# ludusProtoShield.net
KiCad netlist of a schematic drawn in EAGLE
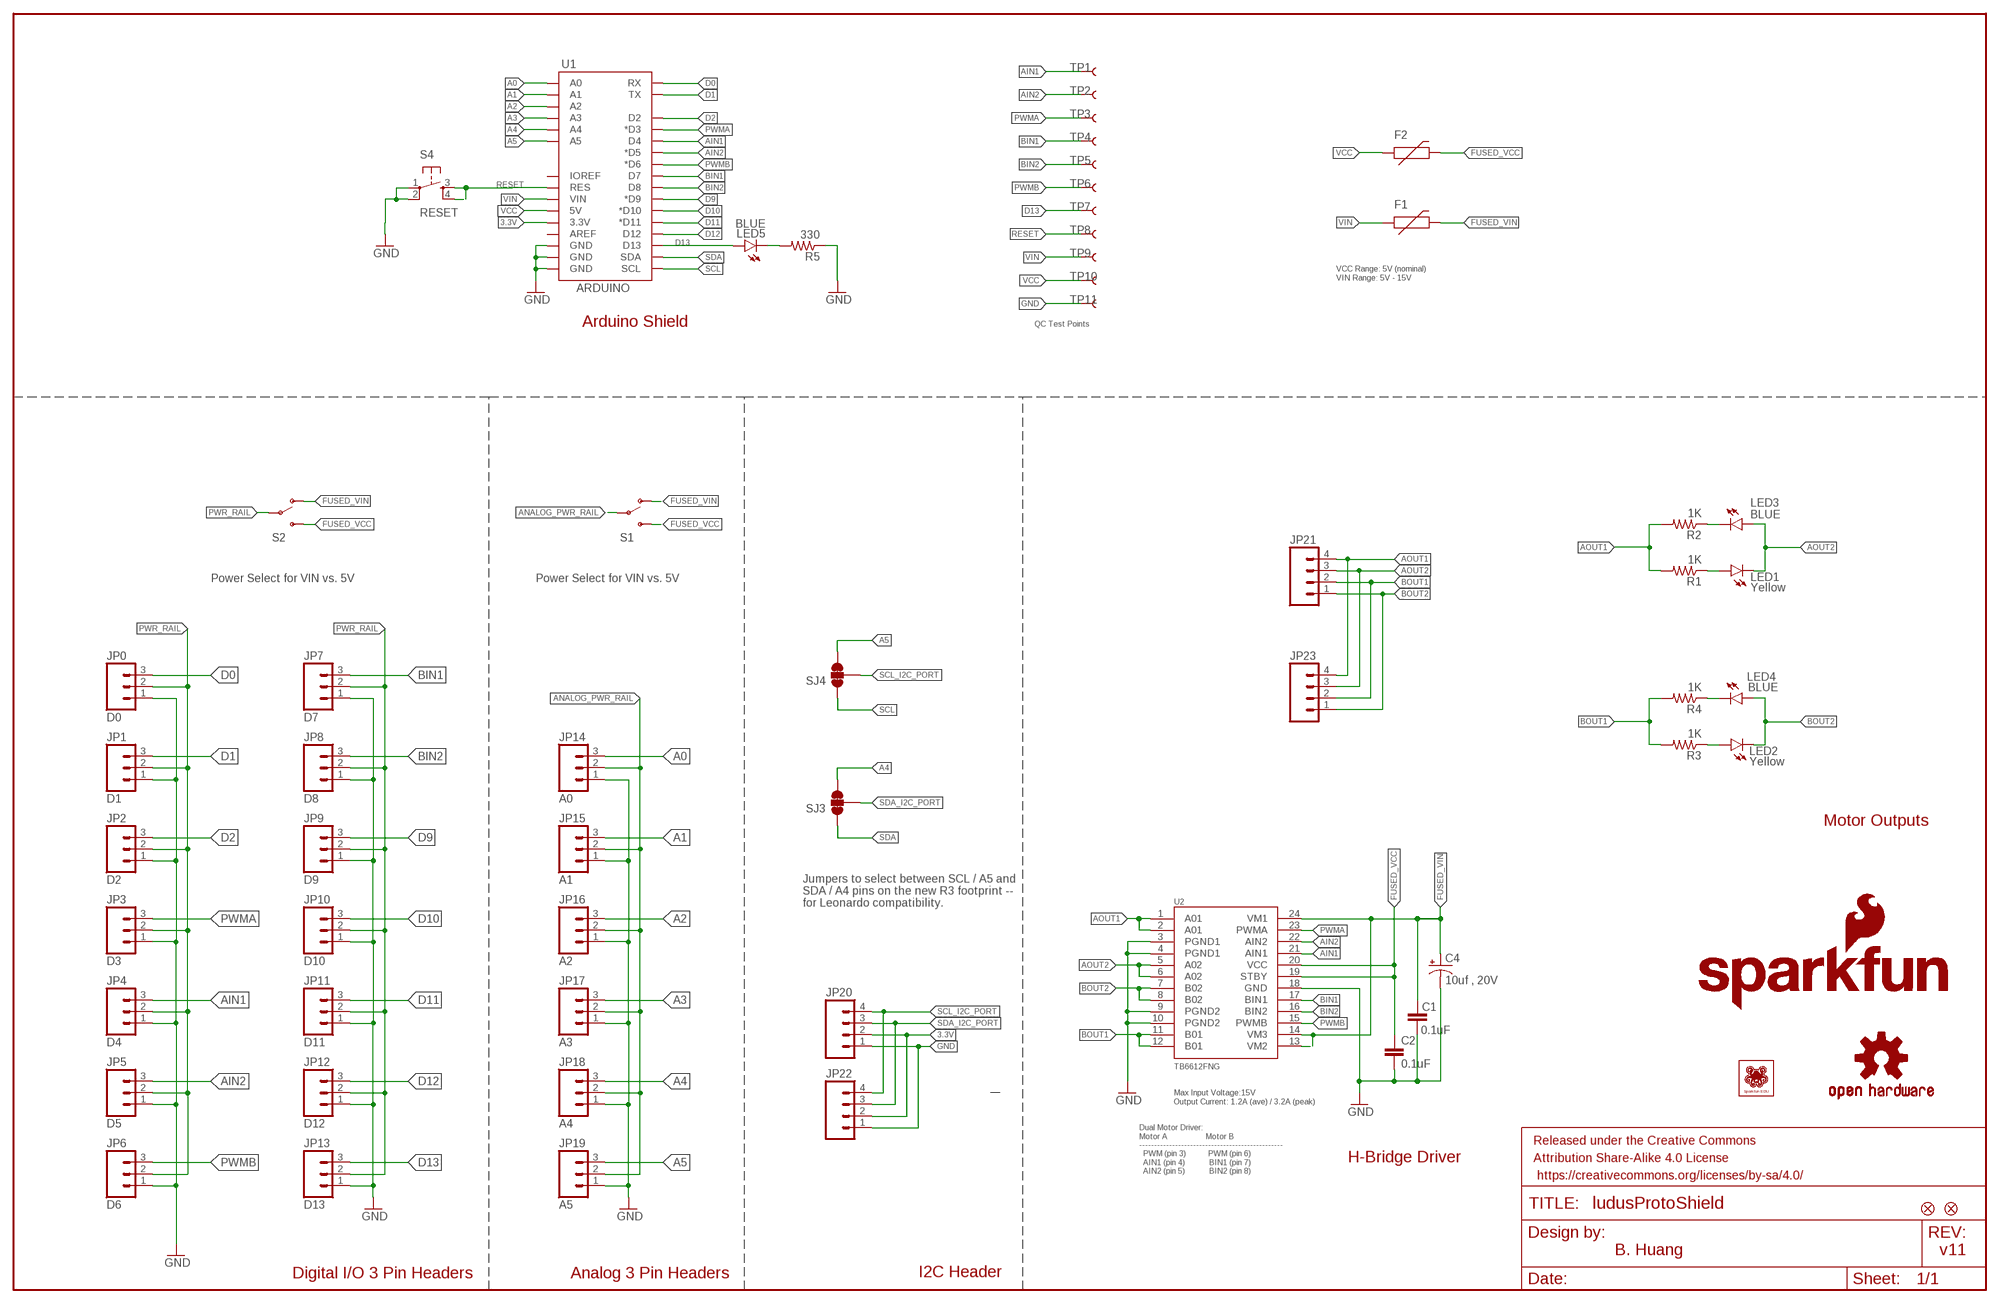
[diagram p0: schematic, sheet 1]

(export (version "E")
  (design (tool "Eeschema 10.0.6"))
  (components
    (comp (ref "C1")
      (value "0.1uF")
      (footprint "eagle-import:0603-CAP")
      (libsource (lib "eagle-import") (part "0.1UF-25V-5%(0603)"))
    )
    (comp (ref "C2")
      (value "0.1uF")
      (footprint "eagle-import:0603-CAP")
      (libsource (lib "eagle-import") (part "0.1UF-25V-5%(0603)"))
    )
    (comp (ref "C4")
      (value "10uf , 20V")
      (footprint "eagle-import:EIA3528")
      (libsource (lib "eagle-import") (part "10UF-20V-10%(TANT)"))
    )
    (comp (ref "F1")
      (value "PTCSMD")
      (footprint "eagle-import:PTC-1206")
      (libsource (lib "eagle-import") (part "PTCSMD"))
    )
    (comp (ref "F2")
      (value "PTCSMD")
      (footprint "eagle-import:PTC-1206")
      (libsource (lib "eagle-import") (part "PTCSMD"))
    )
    (comp (ref "FID1")
      (value "FIDUCIAL1X2")
      (footprint "eagle-import:FIDUCIAL-1X2")
      (libsource (lib "eagle-import") (part "FIDUCIAL1X2"))
    )
    (comp (ref "FID2")
      (value "FIDUCIAL1X2")
      (footprint "eagle-import:FIDUCIAL-1X2")
      (libsource (lib "eagle-import") (part "FIDUCIAL1X2"))
    )
    (comp (ref "FRAME2")
      (value "FRAME-LEDGER")
      (footprint "eagle-import:CREATIVE_COMMONS")
      (libsource (lib "eagle-import") (part "FRAME-LEDGER"))
    )
    (comp (ref "JP0")
      (value "D0")
      (footprint "eagle-import:1X03_LOCK")
      (libsource (lib "eagle-import") (part "M03LOCK"))
    )
    (comp (ref "JP1")
      (value "D1")
      (footprint "eagle-import:1X03_LOCK")
      (libsource (lib "eagle-import") (part "M03LOCK"))
    )
    (comp (ref "JP2")
      (value "D2")
      (footprint "eagle-import:1X03_LOCK")
      (libsource (lib "eagle-import") (part "M03LOCK"))
    )
    (comp (ref "JP3")
      (value "D3")
      (footprint "eagle-import:1X03_LOCK")
      (libsource (lib "eagle-import") (part "M03LOCK"))
    )
    (comp (ref "JP4")
      (value "D4")
      (footprint "eagle-import:1X03_LOCK")
      (libsource (lib "eagle-import") (part "M03LOCK"))
    )
    (comp (ref "JP5")
      (value "D5")
      (footprint "eagle-import:1X03_LOCK")
      (libsource (lib "eagle-import") (part "M03LOCK"))
    )
    (comp (ref "JP6")
      (value "D6")
      (footprint "eagle-import:1X03_LOCK")
      (libsource (lib "eagle-import") (part "M03LOCK"))
    )
    (comp (ref "JP7")
      (value "D7")
      (footprint "eagle-import:1X03_LOCK")
      (libsource (lib "eagle-import") (part "M03LOCK"))
    )
    (comp (ref "JP8")
      (value "D8")
      (footprint "eagle-import:1X03_LOCK")
      (libsource (lib "eagle-import") (part "M03LOCK"))
    )
    (comp (ref "JP9")
      (value "D9")
      (footprint "eagle-import:1X03_LOCK")
      (libsource (lib "eagle-import") (part "M03LOCK"))
    )
    (comp (ref "JP10")
      (value "D10")
      (footprint "eagle-import:1X03_LOCK")
      (libsource (lib "eagle-import") (part "M03LOCK"))
    )
    (comp (ref "JP11")
      (value "D11")
      (footprint "eagle-import:1X03_LOCK")
      (libsource (lib "eagle-import") (part "M03LOCK"))
    )
    (comp (ref "JP12")
      (value "D12")
      (footprint "eagle-import:1X03_LOCK")
      (libsource (lib "eagle-import") (part "M03LOCK"))
    )
    (comp (ref "JP13")
      (value "D13")
      (footprint "eagle-import:1X03_LOCK")
      (libsource (lib "eagle-import") (part "M03LOCK"))
    )
    (comp (ref "JP14")
      (value "A0")
      (footprint "eagle-import:1X03_LOCK")
      (libsource (lib "eagle-import") (part "M03LOCK"))
    )
    (comp (ref "JP15")
      (value "A1")
      (footprint "eagle-import:1X03_LOCK")
      (libsource (lib "eagle-import") (part "M03LOCK"))
    )
    (comp (ref "JP16")
      (value "A2")
      (footprint "eagle-import:1X03_LOCK")
      (libsource (lib "eagle-import") (part "M03LOCK"))
    )
    (comp (ref "JP17")
      (value "A3")
      (footprint "eagle-import:1X03_LOCK")
      (libsource (lib "eagle-import") (part "M03LOCK"))
    )
    (comp (ref "JP18")
      (value "A4")
      (footprint "eagle-import:1X03_LOCK")
      (libsource (lib "eagle-import") (part "M03LOCK"))
    )
    (comp (ref "JP19")
      (value "A5")
      (footprint "eagle-import:1X03_LOCK")
      (libsource (lib "eagle-import") (part "M03LOCK"))
    )
    (comp (ref "JP20")
      (value "M04PTH")
      (footprint "eagle-import:1X04")
      (libsource (lib "eagle-import") (part "M04PTH"))
    )
    (comp (ref "JP21")
      (value "M04PTH")
      (footprint "eagle-import:1X04")
      (libsource (lib "eagle-import") (part "M04PTH"))
    )
    (comp (ref "JP22")
      (value "M04LOCK")
      (footprint "eagle-import:1X04_LOCK")
      (libsource (lib "eagle-import") (part "M04LOCK"))
    )
    (comp (ref "JP23")
      (value "M04LOCK")
      (footprint "eagle-import:1X04_LOCK")
      (libsource (lib "eagle-import") (part "M04LOCK"))
    )
    (comp (ref "LED1")
      (value "Yellow")
      (footprint "eagle-import:LED-0603")
      (libsource (lib "eagle-import") (part "LED-YELLOW0603"))
    )
    (comp (ref "LED2")
      (value "Yellow")
      (footprint "eagle-import:LED-0603")
      (libsource (lib "eagle-import") (part "LED-YELLOW0603"))
    )
    (comp (ref "LED3")
      (value "BLUE")
      (footprint "eagle-import:LED-0603")
      (libsource (lib "eagle-import") (part "LED-BLUE0603"))
    )
    (comp (ref "LED4")
      (value "BLUE")
      (footprint "eagle-import:LED-0603")
      (libsource (lib "eagle-import") (part "LED-BLUE0603"))
    )
    (comp (ref "LED5")
      (value "BLUE")
      (footprint "eagle-import:LED-0603")
      (libsource (lib "eagle-import") (part "LED-BLUE0603"))
    )
    (comp (ref "LOGO1")
      (value "OSHW-LOGOM")
      (footprint "eagle-import:OSHW-LOGO-M")
      (libsource (lib "eagle-import") (part "OSHW-LOGOM"))
    )
    (comp (ref "LOGO2")
      (value "SFE_LOGO_NAME_FLAME.1_INCH")
      (footprint "eagle-import:SFE_LOGO_NAME_FLAME_.1")
      (libsource (lib "eagle-import") (part "SFE_LOGO_NAME_FLAME.1_INCH"))
    )
    (comp (ref "LOGO3")
      (value "SFE_LOGO_FLAME.2COP")
      (footprint "eagle-import:SFE_LOGO_FLAME_COPPER_.2")
      (libsource (lib "eagle-import") (part "SFE_LOGO_FLAME.2COP"))
    )
    (comp (ref "LOGO4")
      (value "SFE_LOGO_NAME_FLAME.1_INCH")
      (footprint "eagle-import:SFE_LOGO_NAME_FLAME_.1")
      (libsource (lib "eagle-import") (part "SFE_LOGO_NAME_FLAME.1_INCH"))
    )
    (comp (ref "R1")
      (value "1K")
      (footprint "eagle-import:0603-RES")
      (libsource (lib "eagle-import") (part "1KOHM-1/10W-1%(0603)"))
    )
    (comp (ref "R2")
      (value "1K")
      (footprint "eagle-import:0603-RES")
      (libsource (lib "eagle-import") (part "1KOHM-1/10W-1%(0603)"))
    )
    (comp (ref "R3")
      (value "1K")
      (footprint "eagle-import:0603-RES")
      (libsource (lib "eagle-import") (part "1KOHM-1/10W-1%(0603)"))
    )
    (comp (ref "R4")
      (value "1K")
      (footprint "eagle-import:0603-RES")
      (libsource (lib "eagle-import") (part "1KOHM-1/10W-1%(0603)"))
    )
    (comp (ref "R5")
      (value "330")
      (footprint "eagle-import:0603-RES")
      (libsource (lib "eagle-import") (part "330OHM1/10W1%(0603)"))
    )
    (comp (ref "S1")
      (value "SWITCH-SPDTSMD")
      (footprint "eagle-import:AYZ0202")
      (libsource (lib "eagle-import") (part "SWITCH-SPDTSMD"))
    )
    (comp (ref "S2")
      (value "SWITCH-SPDTSMD")
      (footprint "eagle-import:AYZ0202")
      (libsource (lib "eagle-import") (part "SWITCH-SPDTSMD"))
    )
    (comp (ref "S4")
      (value "RESET")
      (footprint "eagle-import:TACTILE-SWITCH-SMD")
      (libsource (lib "eagle-import") (part "TAC_SWITCHSMD"))
    )
    (comp (ref "SJ3")
      (value "JUMPER-PAD-3-NC_BY_TRACE")
      (footprint "eagle-import:PAD-JUMPER-3-3OF3_NC_BY_TRACE_YES_SILK_FULL_BOX")
      (libsource (lib "eagle-import") (part "JUMPER-PAD-3-NC_BY_TRACE"))
    )
    (comp (ref "SJ4")
      (value "JUMPER-PAD-3-NC_BY_TRACE")
      (footprint "eagle-import:PAD-JUMPER-3-3OF3_NC_BY_TRACE_YES_SILK_FULL_BOX")
      (libsource (lib "eagle-import") (part "JUMPER-PAD-3-NC_BY_TRACE"))
    )
    (comp (ref "TP1")
      (value "TEST-POINT3X5")
      (footprint "eagle-import:PAD.03X.05")
      (libsource (lib "eagle-import") (part "TEST-POINT3X5"))
    )
    (comp (ref "TP2")
      (value "TEST-POINT3X5")
      (footprint "eagle-import:PAD.03X.05")
      (libsource (lib "eagle-import") (part "TEST-POINT3X5"))
    )
    (comp (ref "TP3")
      (value "TEST-POINT3X5")
      (footprint "eagle-import:PAD.03X.05")
      (libsource (lib "eagle-import") (part "TEST-POINT3X5"))
    )
    (comp (ref "TP4")
      (value "TEST-POINT3X5")
      (footprint "eagle-import:PAD.03X.05")
      (libsource (lib "eagle-import") (part "TEST-POINT3X5"))
    )
    (comp (ref "TP5")
      (value "TEST-POINT3X5")
      (footprint "eagle-import:PAD.03X.05")
      (libsource (lib "eagle-import") (part "TEST-POINT3X5"))
    )
    (comp (ref "TP6")
      (value "TEST-POINT3X5")
      (footprint "eagle-import:PAD.03X.05")
      (libsource (lib "eagle-import") (part "TEST-POINT3X5"))
    )
    (comp (ref "TP7")
      (value "TEST-POINT3X5")
      (footprint "eagle-import:PAD.03X.05")
      (libsource (lib "eagle-import") (part "TEST-POINT3X5"))
    )
    (comp (ref "TP8")
      (value "TEST-POINT3X5")
      (footprint "eagle-import:PAD.03X.05")
      (libsource (lib "eagle-import") (part "TEST-POINT3X5"))
    )
    (comp (ref "TP9")
      (value "TEST-POINT3X5")
      (footprint "eagle-import:PAD.03X.05")
      (libsource (lib "eagle-import") (part "TEST-POINT3X5"))
    )
    (comp (ref "TP10")
      (value "TEST-POINT3X5")
      (footprint "eagle-import:PAD.03X.05")
      (libsource (lib "eagle-import") (part "TEST-POINT3X5"))
    )
    (comp (ref "TP11")
      (value "TEST-POINT3X5")
      (footprint "eagle-import:PAD.03X.05")
      (libsource (lib "eagle-import") (part "TEST-POINT3X5"))
    )
    (comp (ref "U$1")
      (value "SFE_LUDUSSFE_LUDUS-M")
      (footprint "eagle-import:SFE_LUDUS-M")
      (libsource (lib "eagle-import") (part "SFE_LUDUSSFE_LUDUS-M"))
    )
    (comp (ref "U1")
      (value "ARDUINO")
      (footprint "eagle-import:UNO_R3_SHIELD_NOLABELS_LOCK")
      (libsource (lib "eagle-import") (part "ARDUINO_R3_SHIELDUNO_R3_SHIELD_NOLABELS_LOCK"))
    )
    (comp (ref "U2")
      (value "TB6612FNG")
      (footprint "eagle-import:SSOP24")
      (libsource (lib "eagle-import") (part "TB6612FNG"))
    )
  )
  (nets
    (net (code "1") (name "3.3V") (class "Default")
      (node (ref "JP20") (pin "2") (pinfunction "2_2") (pintype "passive"))
      (node (ref "JP22") (pin "2") (pinfunction "2_2") (pintype "passive"))
      (node (ref "U1") (pin "3.3V") (pinfunction "3.3V_3.3V") (pintype "bidirectional"))
    )
    (net (code "2") (name "A0") (class "Default")
      (node (ref "JP14") (pin "3") (pinfunction "3_3") (pintype "passive"))
      (node (ref "U1") (pin "A0") (pinfunction "A0_A0") (pintype "bidirectional"))
    )
    (net (code "3") (name "A1") (class "Default")
      (node (ref "JP15") (pin "3") (pinfunction "3_3") (pintype "passive"))
      (node (ref "U1") (pin "A1") (pinfunction "A1_A1") (pintype "bidirectional"))
    )
    (net (code "4") (name "A2") (class "Default")
      (node (ref "JP16") (pin "3") (pinfunction "3_3") (pintype "passive"))
      (node (ref "U1") (pin "A2") (pinfunction "A2_A2") (pintype "bidirectional"))
    )
    (net (code "5") (name "A3") (class "Default")
      (node (ref "JP17") (pin "3") (pinfunction "3_3") (pintype "passive"))
      (node (ref "U1") (pin "A3") (pinfunction "A3_A3") (pintype "bidirectional"))
    )
    (net (code "6") (name "A4") (class "Default")
      (node (ref "JP18") (pin "3") (pinfunction "3_3") (pintype "passive"))
      (node (ref "SJ3") (pin "3") (pinfunction "3_3") (pintype "passive"))
      (node (ref "U1") (pin "A4") (pinfunction "A4_A4") (pintype "bidirectional"))
    )
    (net (code "7") (name "A5") (class "Default")
      (node (ref "JP19") (pin "3") (pinfunction "3_3") (pintype "passive"))
      (node (ref "SJ4") (pin "3") (pinfunction "3_3") (pintype "passive"))
      (node (ref "U1") (pin "A5") (pinfunction "A5_A5") (pintype "bidirectional"))
    )
    (net (code "8") (name "AIN1") (class "Default")
      (node (ref "JP4") (pin "3") (pinfunction "3_3") (pintype "passive"))
      (node (ref "TP1") (pin "P$1") (pinfunction "1_P$1") (pintype "bidirectional"))
      (node (ref "U1") (pin "D4") (pinfunction "D4_D4") (pintype "bidirectional"))
      (node (ref "U2") (pin "21") (pinfunction "AIN1_21") (pintype "bidirectional"))
    )
    (net (code "9") (name "AIN2") (class "Default")
      (node (ref "JP5") (pin "3") (pinfunction "3_3") (pintype "passive"))
      (node (ref "TP2") (pin "P$1") (pinfunction "1_P$1") (pintype "bidirectional"))
      (node (ref "U1") (pin "D5") (pinfunction "*D5_D5") (pintype "bidirectional"))
      (node (ref "U2") (pin "22") (pinfunction "AIN2_22") (pintype "bidirectional"))
    )
    (net (code "10") (name "ANALOG_PWR_RAIL") (class "Default")
      (node (ref "JP14") (pin "2") (pinfunction "2_2") (pintype "passive"))
      (node (ref "JP15") (pin "2") (pinfunction "2_2") (pintype "passive"))
      (node (ref "JP16") (pin "2") (pinfunction "2_2") (pintype "passive"))
      (node (ref "JP17") (pin "2") (pinfunction "2_2") (pintype "passive"))
      (node (ref "JP18") (pin "2") (pinfunction "2_2") (pintype "passive"))
      (node (ref "JP19") (pin "2") (pinfunction "2_2") (pintype "passive"))
      (node (ref "S1") (pin "2") (pinfunction "P_2") (pintype "passive"))
    )
    (net (code "11") (name "AOUT1") (class "Default")
      (node (ref "JP21") (pin "4") (pinfunction "4_4") (pintype "passive"))
      (node (ref "JP23") (pin "4") (pinfunction "4_4") (pintype "passive"))
      (node (ref "R1") (pin "2") (pinfunction "2_2") (pintype "passive"))
      (node (ref "R2") (pin "2") (pinfunction "2_2") (pintype "passive"))
      (node (ref "U2") (pin "1") (pinfunction "A01_1") (pintype "bidirectional"))
      (node (ref "U2") (pin "2") (pinfunction "A01_2") (pintype "bidirectional"))
    )
    (net (code "12") (name "AOUT2") (class "Default")
      (node (ref "JP21") (pin "3") (pinfunction "3_3") (pintype "passive"))
      (node (ref "JP23") (pin "3") (pinfunction "3_3") (pintype "passive"))
      (node (ref "LED1") (pin "C") (pinfunction "C_C") (pintype "passive"))
      (node (ref "LED3") (pin "A") (pinfunction "A_A") (pintype "passive"))
      (node (ref "U2") (pin "5") (pinfunction "A02_5") (pintype "bidirectional"))
      (node (ref "U2") (pin "6") (pinfunction "A02_6") (pintype "bidirectional"))
    )
    (net (code "13") (name "BIN1") (class "Default")
      (node (ref "JP7") (pin "3") (pinfunction "3_3") (pintype "passive"))
      (node (ref "TP4") (pin "P$1") (pinfunction "1_P$1") (pintype "bidirectional"))
      (node (ref "U1") (pin "D7") (pinfunction "D7_D7") (pintype "bidirectional"))
      (node (ref "U2") (pin "17") (pinfunction "BIN1_17") (pintype "bidirectional"))
    )
    (net (code "14") (name "BIN2") (class "Default")
      (node (ref "JP8") (pin "3") (pinfunction "3_3") (pintype "passive"))
      (node (ref "TP5") (pin "P$1") (pinfunction "1_P$1") (pintype "bidirectional"))
      (node (ref "U1") (pin "D8") (pinfunction "D8_D8") (pintype "bidirectional"))
      (node (ref "U2") (pin "16") (pinfunction "BIN2_16") (pintype "bidirectional"))
    )
    (net (code "15") (name "BOUT1") (class "Default")
      (node (ref "JP21") (pin "2") (pinfunction "2_2") (pintype "passive"))
      (node (ref "JP23") (pin "2") (pinfunction "2_2") (pintype "passive"))
      (node (ref "R3") (pin "2") (pinfunction "2_2") (pintype "passive"))
      (node (ref "R4") (pin "2") (pinfunction "2_2") (pintype "passive"))
      (node (ref "U2") (pin "11") (pinfunction "B01_11") (pintype "bidirectional"))
      (node (ref "U2") (pin "12") (pinfunction "B01_12") (pintype "bidirectional"))
    )
    (net (code "16") (name "BOUT2") (class "Default")
      (node (ref "JP21") (pin "1") (pinfunction "1_1") (pintype "passive"))
      (node (ref "JP23") (pin "1") (pinfunction "1_1") (pintype "passive"))
      (node (ref "LED2") (pin "C") (pinfunction "C_C") (pintype "passive"))
      (node (ref "LED4") (pin "A") (pinfunction "A_A") (pintype "passive"))
      (node (ref "U2") (pin "7") (pinfunction "B02_7") (pintype "bidirectional"))
      (node (ref "U2") (pin "8") (pinfunction "B02_8") (pintype "bidirectional"))
    )
    (net (code "17") (name "D0") (class "Default")
      (node (ref "JP0") (pin "3") (pinfunction "3_3") (pintype "passive"))
      (node (ref "U1") (pin "RX") (pinfunction "RX_RX") (pintype "bidirectional"))
    )
    (net (code "18") (name "D1") (class "Default")
      (node (ref "JP1") (pin "3") (pinfunction "3_3") (pintype "passive"))
      (node (ref "U1") (pin "TX") (pinfunction "TX_TX") (pintype "bidirectional"))
    )
    (net (code "19") (name "D2") (class "Default")
      (node (ref "JP2") (pin "3") (pinfunction "3_3") (pintype "passive"))
      (node (ref "U1") (pin "D2") (pinfunction "D2_D2") (pintype "bidirectional"))
    )
    (net (code "20") (name "D9") (class "Default")
      (node (ref "JP9") (pin "3") (pinfunction "3_3") (pintype "passive"))
      (node (ref "U1") (pin "D9") (pinfunction "*D9_D9") (pintype "bidirectional"))
    )
    (net (code "21") (name "D10") (class "Default")
      (node (ref "JP10") (pin "3") (pinfunction "3_3") (pintype "passive"))
      (node (ref "U1") (pin "D10") (pinfunction "*D10_D10") (pintype "bidirectional"))
    )
    (net (code "22") (name "D11") (class "Default")
      (node (ref "JP11") (pin "3") (pinfunction "3_3") (pintype "passive"))
      (node (ref "U1") (pin "D11") (pinfunction "*D11_D11") (pintype "bidirectional"))
    )
    (net (code "23") (name "D12") (class "Default")
      (node (ref "JP12") (pin "3") (pinfunction "3_3") (pintype "passive"))
      (node (ref "U1") (pin "D12") (pinfunction "D12_D12") (pintype "bidirectional"))
    )
    (net (code "24") (name "D13") (class "Default")
      (node (ref "JP13") (pin "3") (pinfunction "3_3") (pintype "passive"))
      (node (ref "LED5") (pin "A") (pinfunction "A_A") (pintype "passive"))
      (node (ref "TP7") (pin "P$1") (pinfunction "1_P$1") (pintype "bidirectional"))
      (node (ref "U1") (pin "D13") (pinfunction "D13_D13") (pintype "bidirectional"))
    )
    (net (code "25") (name "FUSED_VCC") (class "Default")
      (node (ref "C2") (pin "1") (pinfunction "1_1") (pintype "passive"))
      (node (ref "F2") (pin "2") (pinfunction "2_2") (pintype "bidirectional"))
      (node (ref "S1") (pin "3") (pinfunction "S_3") (pintype "passive"))
      (node (ref "S2") (pin "3") (pinfunction "S_3") (pintype "passive"))
      (node (ref "U2") (pin "19") (pinfunction "STBY_19") (pintype "bidirectional"))
      (node (ref "U2") (pin "20") (pinfunction "VCC_20") (pintype "bidirectional"))
    )
    (net (code "26") (name "FUSED_VIN") (class "Default")
      (node (ref "C1") (pin "1") (pinfunction "1_1") (pintype "passive"))
      (node (ref "C4") (pin "A") (pinfunction "+_A") (pintype "passive"))
      (node (ref "F1") (pin "2") (pinfunction "2_2") (pintype "bidirectional"))
      (node (ref "S1") (pin "1") (pinfunction "O_1") (pintype "passive"))
      (node (ref "S2") (pin "1") (pinfunction "O_1") (pintype "passive"))
      (node (ref "U2") (pin "13") (pinfunction "VM2_13") (pintype "bidirectional"))
      (node (ref "U2") (pin "14") (pinfunction "VM3_14") (pintype "bidirectional"))
      (node (ref "U2") (pin "24") (pinfunction "VM1_24") (pintype "bidirectional"))
    )
    (net (code "27") (name "GND") (class "Default")
      (node (ref "C1") (pin "2") (pinfunction "2_2") (pintype "passive"))
      (node (ref "C2") (pin "2") (pinfunction "2_2") (pintype "passive"))
      (node (ref "C4") (pin "C") (pinfunction "-_C") (pintype "passive"))
      (node (ref "JP0") (pin "1") (pinfunction "1_1") (pintype "passive"))
      (node (ref "JP1") (pin "1") (pinfunction "1_1") (pintype "passive"))
      (node (ref "JP10") (pin "1") (pinfunction "1_1") (pintype "passive"))
      (node (ref "JP11") (pin "1") (pinfunction "1_1") (pintype "passive"))
      (node (ref "JP12") (pin "1") (pinfunction "1_1") (pintype "passive"))
      (node (ref "JP13") (pin "1") (pinfunction "1_1") (pintype "passive"))
      (node (ref "JP14") (pin "1") (pinfunction "1_1") (pintype "passive"))
      (node (ref "JP15") (pin "1") (pinfunction "1_1") (pintype "passive"))
      (node (ref "JP16") (pin "1") (pinfunction "1_1") (pintype "passive"))
      (node (ref "JP17") (pin "1") (pinfunction "1_1") (pintype "passive"))
      (node (ref "JP18") (pin "1") (pinfunction "1_1") (pintype "passive"))
      (node (ref "JP19") (pin "1") (pinfunction "1_1") (pintype "passive"))
      (node (ref "JP2") (pin "1") (pinfunction "1_1") (pintype "passive"))
      (node (ref "JP20") (pin "1") (pinfunction "1_1") (pintype "passive"))
      (node (ref "JP22") (pin "1") (pinfunction "1_1") (pintype "passive"))
      (node (ref "JP3") (pin "1") (pinfunction "1_1") (pintype "passive"))
      (node (ref "JP4") (pin "1") (pinfunction "1_1") (pintype "passive"))
      (node (ref "JP5") (pin "1") (pinfunction "1_1") (pintype "passive"))
      (node (ref "JP6") (pin "1") (pinfunction "1_1") (pintype "passive"))
      (node (ref "JP7") (pin "1") (pinfunction "1_1") (pintype "passive"))
      (node (ref "JP8") (pin "1") (pinfunction "1_1") (pintype "passive"))
      (node (ref "JP9") (pin "1") (pinfunction "1_1") (pintype "passive"))
      (node (ref "R5") (pin "1") (pinfunction "1_1") (pintype "passive"))
      (node (ref "S4") (pin "1") (pinfunction "1_1") (pintype "passive"))
      (node (ref "S4") (pin "2") (pinfunction "2_2") (pintype "passive"))
      (node (ref "TP11") (pin "P$1") (pinfunction "1_P$1") (pintype "bidirectional"))
      (node (ref "U1") (pin "GND@0") (pinfunction "GND_GND@0") (pintype "bidirectional"))
      (node (ref "U1") (pin "GND@1") (pinfunction "GND_GND@1") (pintype "bidirectional"))
      (node (ref "U1") (pin "GND@2") (pinfunction "GND_GND@2") (pintype "bidirectional"))
      (node (ref "U2") (pin "10") (pinfunction "PGND2_10") (pintype "bidirectional"))
      (node (ref "U2") (pin "18") (pinfunction "GND_18") (pintype "bidirectional"))
      (node (ref "U2") (pin "3") (pinfunction "PGND1_3") (pintype "bidirectional"))
      (node (ref "U2") (pin "4") (pinfunction "PGND1_4") (pintype "bidirectional"))
      (node (ref "U2") (pin "9") (pinfunction "PGND2_9") (pintype "bidirectional"))
    )
    (net (code "28") (name "Net-(LED1-PadA)") (class "Default")
      (node (ref "LED1") (pin "A") (pinfunction "A_A") (pintype "passive"))
      (node (ref "R1") (pin "1") (pinfunction "1_1") (pintype "passive"))
    )
    (net (code "29") (name "Net-(LED2-PadA)") (class "Default")
      (node (ref "LED2") (pin "A") (pinfunction "A_A") (pintype "passive"))
      (node (ref "R3") (pin "1") (pinfunction "1_1") (pintype "passive"))
    )
    (net (code "30") (name "Net-(LED3-PadC)") (class "Default")
      (node (ref "LED3") (pin "C") (pinfunction "C_C") (pintype "passive"))
      (node (ref "R2") (pin "1") (pinfunction "1_1") (pintype "passive"))
    )
    (net (code "31") (name "Net-(LED4-PadC)") (class "Default")
      (node (ref "LED4") (pin "C") (pinfunction "C_C") (pintype "passive"))
      (node (ref "R4") (pin "1") (pinfunction "1_1") (pintype "passive"))
    )
    (net (code "32") (name "Net-(LED5-PadC)") (class "Default")
      (node (ref "LED5") (pin "C") (pinfunction "C_C") (pintype "passive"))
      (node (ref "R5") (pin "2") (pinfunction "2_2") (pintype "passive"))
    )
    (net (code "33") (name "PWMA") (class "Default")
      (node (ref "JP3") (pin "3") (pinfunction "3_3") (pintype "passive"))
      (node (ref "TP3") (pin "P$1") (pinfunction "1_P$1") (pintype "bidirectional"))
      (node (ref "U1") (pin "D3") (pinfunction "*D3_D3") (pintype "bidirectional"))
      (node (ref "U2") (pin "23") (pinfunction "PWMA_23") (pintype "bidirectional"))
    )
    (net (code "34") (name "PWMB") (class "Default")
      (node (ref "JP6") (pin "3") (pinfunction "3_3") (pintype "passive"))
      (node (ref "TP6") (pin "P$1") (pinfunction "1_P$1") (pintype "bidirectional"))
      (node (ref "U1") (pin "D6") (pinfunction "*D6_D6") (pintype "bidirectional"))
      (node (ref "U2") (pin "15") (pinfunction "PWMB_15") (pintype "bidirectional"))
    )
    (net (code "35") (name "PWR_RAIL") (class "Default")
      (node (ref "JP0") (pin "2") (pinfunction "2_2") (pintype "passive"))
      (node (ref "JP1") (pin "2") (pinfunction "2_2") (pintype "passive"))
      (node (ref "JP10") (pin "2") (pinfunction "2_2") (pintype "passive"))
      (node (ref "JP11") (pin "2") (pinfunction "2_2") (pintype "passive"))
      (node (ref "JP12") (pin "2") (pinfunction "2_2") (pintype "passive"))
      (node (ref "JP13") (pin "2") (pinfunction "2_2") (pintype "passive"))
      (node (ref "JP2") (pin "2") (pinfunction "2_2") (pintype "passive"))
      (node (ref "JP3") (pin "2") (pinfunction "2_2") (pintype "passive"))
      (node (ref "JP4") (pin "2") (pinfunction "2_2") (pintype "passive"))
      (node (ref "JP5") (pin "2") (pinfunction "2_2") (pintype "passive"))
      (node (ref "JP6") (pin "2") (pinfunction "2_2") (pintype "passive"))
      (node (ref "JP7") (pin "2") (pinfunction "2_2") (pintype "passive"))
      (node (ref "JP8") (pin "2") (pinfunction "2_2") (pintype "passive"))
      (node (ref "JP9") (pin "2") (pinfunction "2_2") (pintype "passive"))
      (node (ref "S2") (pin "2") (pinfunction "P_2") (pintype "passive"))
    )
    (net (code "36") (name "RESET") (class "Default")
      (node (ref "S4") (pin "3") (pinfunction "3_3") (pintype "passive"))
      (node (ref "S4") (pin "4") (pinfunction "4_4") (pintype "passive"))
      (node (ref "TP8") (pin "P$1") (pinfunction "1_P$1") (pintype "bidirectional"))
      (node (ref "U1") (pin "RES") (pinfunction "RES_RES") (pintype "bidirectional"))
    )
    (net (code "37") (name "SCL") (class "Default")
      (node (ref "SJ4") (pin "1") (pinfunction "1_1") (pintype "passive"))
      (node (ref "U1") (pin "SCL") (pinfunction "SCL_SCL") (pintype "bidirectional"))
    )
    (net (code "38") (name "SCL_I2C_PORT") (class "Default")
      (node (ref "JP20") (pin "4") (pinfunction "4_4") (pintype "passive"))
      (node (ref "JP22") (pin "4") (pinfunction "4_4") (pintype "passive"))
      (node (ref "SJ4") (pin "2") (pinfunction "2_2") (pintype "passive"))
    )
    (net (code "39") (name "SDA") (class "Default")
      (node (ref "SJ3") (pin "1") (pinfunction "1_1") (pintype "passive"))
      (node (ref "U1") (pin "SDA") (pinfunction "SDA_SDA") (pintype "bidirectional"))
    )
    (net (code "40") (name "SDA_I2C_PORT") (class "Default")
      (node (ref "JP20") (pin "3") (pinfunction "3_3") (pintype "passive"))
      (node (ref "JP22") (pin "3") (pinfunction "3_3") (pintype "passive"))
      (node (ref "SJ3") (pin "2") (pinfunction "2_2") (pintype "passive"))
    )
    (net (code "41") (name "VCC") (class "Default")
      (node (ref "F2") (pin "1") (pinfunction "1_1") (pintype "bidirectional"))
      (node (ref "TP10") (pin "P$1") (pinfunction "1_P$1") (pintype "bidirectional"))
      (node (ref "U1") (pin "5V") (pinfunction "5V_5V") (pintype "bidirectional"))
    )
    (net (code "42") (name "VIN") (class "Default")
      (node (ref "F1") (pin "1") (pinfunction "1_1") (pintype "bidirectional"))
      (node (ref "TP9") (pin "P$1") (pinfunction "1_P$1") (pintype "bidirectional"))
      (node (ref "U1") (pin "VIN") (pinfunction "VIN_VIN") (pintype "bidirectional"))
    )
    (net (code "43") (name "unconnected-(U1-PadAREF)") (class "Default")
      (node (ref "U1") (pin "AREF") (pinfunction "AREF_AREF") (pintype "bidirectional"))
    )
    (net (code "44") (name "unconnected-(U1-PadIOREF)") (class "Default")
      (node (ref "U1") (pin "IOREF") (pinfunction "IOREF_IOREF") (pintype "bidirectional"))
    )
  )
)
